# DM3370_Connector_B.net
KiCad netlist of a schematic drawn in Altium Designer
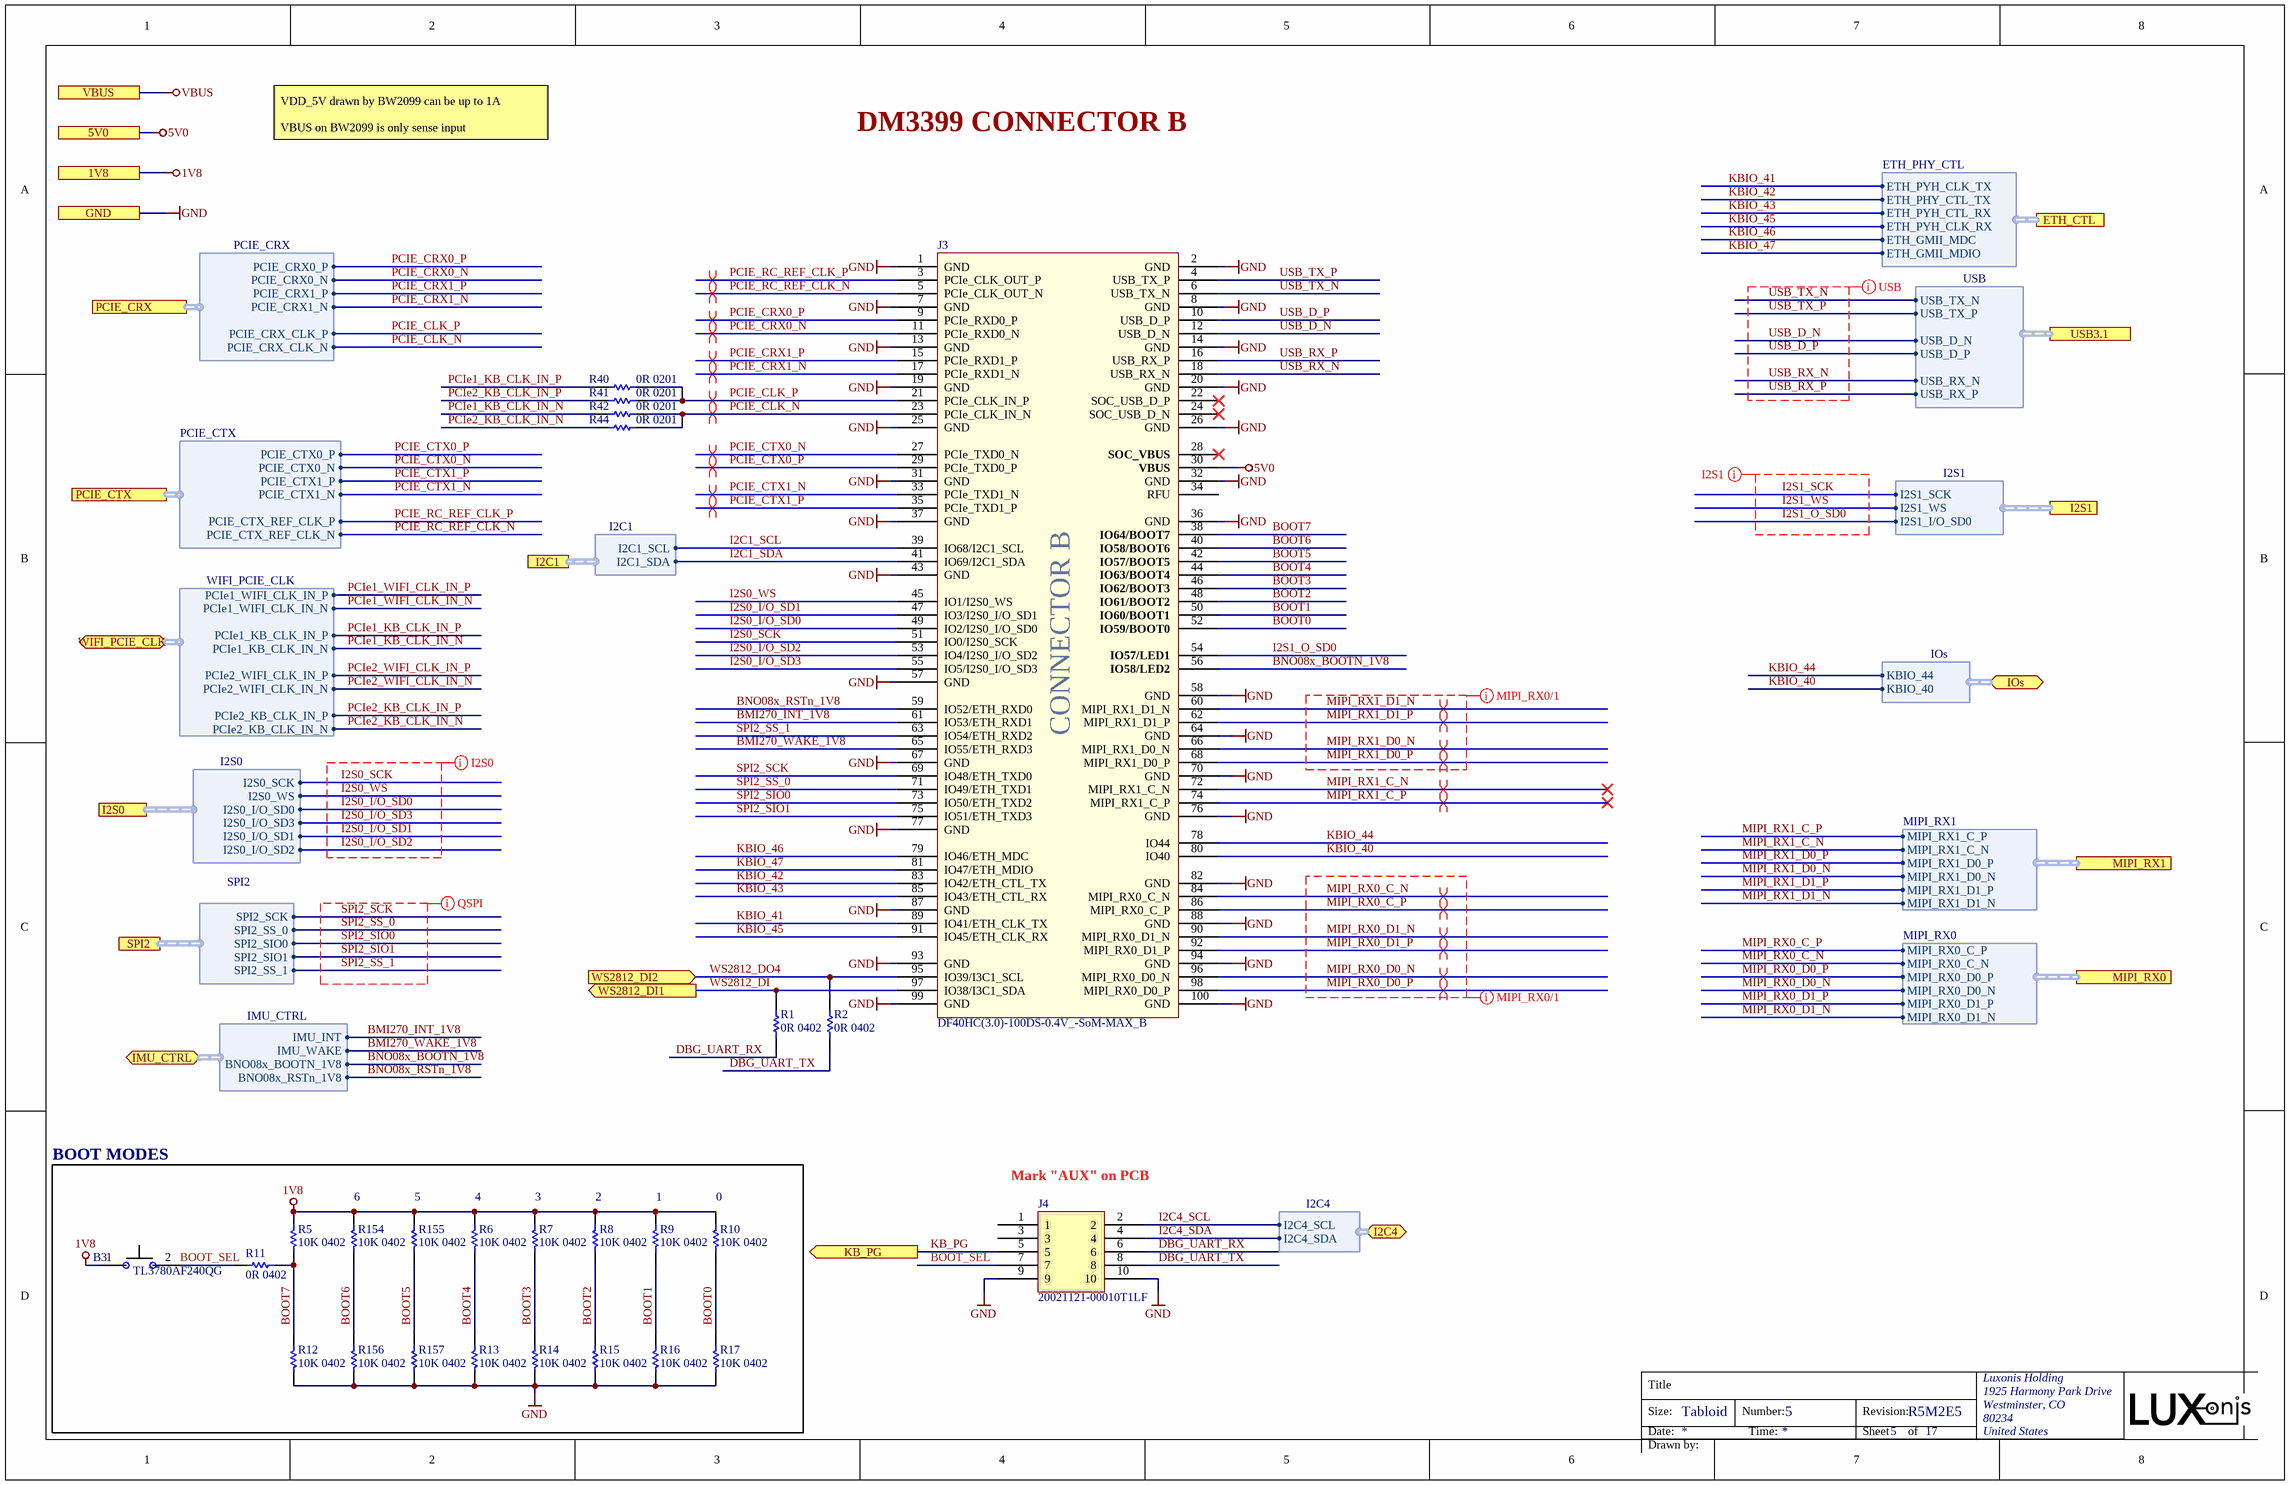
[diagram p0: DM3370_Connector_B.SchDoc]

(export (version "E")
  (design (tool "Eeschema 10.0.6"))
  (components
    (comp (ref "B3")
      (value "TL3780AF240QG")
      (footprint "TL3780AF240QG-Footprint-1")
      (libsource (lib "Luxonis LLC") (part "TL3780AF240QG"))
    )
    (comp (ref "J3")
      (value "DF40HC(3.0)-100DS-0.4V_-SoM-MAX_B")
      (footprint "SOM_MAX_CONN_B_DF40HC-3.0-100DS-0.4V_minpad")
      (description "OAK-SoM-MAX base board conn. B")
      (fields (field (name "SOURCE") "LuxonisMaster_nejc.SchLib"))
      (libsource (lib "Luxonis LLC") (part "DF40HC(3.0)-100DS-0.4V_-SoM-MAX_B"))
    )
    (comp (ref "J4")
      (value "20021121-00010T1LF")
      (footprint "LuxonisMaster:20021121-00010T1LF")
      (description "CONN HEADER SMD 10POS 1.27MM")
      (libsource (lib "LuxonisMaster") (part "20021121-00010T1LF"))
    )
    (comp (ref "R1")
      (value "0R 0402")
      (footprint "RES_Altium_Vault_Generic:RESC0402(1005)_L")
      (description "RES SMD 0 OHM JUMPER 1/16W 0402")
      (fields (field (name "TOLERANCE") "5%"))
      (libsource (lib "LuxonisMaster") (part "CRCW04020000Z0ED"))
    )
    (comp (ref "R2")
      (value "0R 0402")
      (footprint "RES_Altium_Vault_Generic:RESC0402(1005)_L")
      (description "RES SMD 0 OHM JUMPER 1/16W 0402")
      (fields (field (name "TOLERANCE") "5%"))
      (libsource (lib "LuxonisMaster") (part "CRCW04020000Z0ED"))
    )
    (comp (ref "R5")
      (value "10K 0402")
      (footprint "RES_Altium_Vault_Generic:RESC0402(1005)_L")
      (fields (field (name "TOLERANCE") "1%"))
      (libsource (lib "LuxonisMaster") (part "RC0402FR-1310KL"))
    )
    (comp (ref "R6")
      (value "10K 0402")
      (footprint "RES_Altium_Vault_Generic:RESC0402(1005)_L")
      (fields (field (name "TOLERANCE") "1%"))
      (libsource (lib "LuxonisMaster") (part "RC0402FR-1310KL"))
    )
    (comp (ref "R7")
      (value "10K 0402")
      (footprint "RES_Altium_Vault_Generic:RESC0402(1005)_L")
      (fields (field (name "TOLERANCE") "1%"))
      (libsource (lib "LuxonisMaster") (part "RC0402FR-1310KL"))
    )
    (comp (ref "R8")
      (value "10K 0402")
      (footprint "RES_Altium_Vault_Generic:RESC0402(1005)_L")
      (fields (field (name "TOLERANCE") "1%"))
      (libsource (lib "LuxonisMaster") (part "RC0402FR-1310KL"))
    )
    (comp (ref "R9")
      (value "10K 0402")
      (footprint "RES_Altium_Vault_Generic:RESC0402(1005)_L")
      (fields (field (name "TOLERANCE") "1%"))
      (libsource (lib "LuxonisMaster") (part "RC0402FR-1310KL"))
    )
    (comp (ref "R10")
      (value "10K 0402")
      (footprint "RES_Altium_Vault_Generic:RESC0402(1005)_L")
      (fields (field (name "TOLERANCE") "1%"))
      (libsource (lib "LuxonisMaster") (part "RC0402FR-1310KL"))
    )
    (comp (ref "R11")
      (value "0R 0402")
      (footprint "RES_Altium_Vault_Generic:RESC0402(1005)_L")
      (description "RES SMD 0 OHM JUMPER 1/16W 0402")
      (fields (field (name "TOLERANCE") "5%"))
      (libsource (lib "LuxonisMaster") (part "CRCW04020000Z0ED"))
    )
    (comp (ref "R12")
      (value "10K 0402")
      (footprint "RES_Altium_Vault_Generic:RESC0402(1005)_L")
      (fields (field (name "TOLERANCE") "1%"))
      (libsource (lib "LuxonisMaster") (part "RC0402FR-1310KL"))
    )
    (comp (ref "R13")
      (value "10K 0402")
      (footprint "RES_Altium_Vault_Generic:RESC0402(1005)_L")
      (fields (field (name "TOLERANCE") "1%"))
      (libsource (lib "LuxonisMaster") (part "RC0402FR-1310KL"))
    )
    (comp (ref "R14")
      (value "10K 0402")
      (footprint "RES_Altium_Vault_Generic:RESC0402(1005)_L")
      (fields (field (name "TOLERANCE") "1%"))
      (libsource (lib "LuxonisMaster") (part "RC0402FR-1310KL"))
    )
    (comp (ref "R15")
      (value "10K 0402")
      (footprint "RES_Altium_Vault_Generic:RESC0402(1005)_L")
      (fields (field (name "TOLERANCE") "1%"))
      (libsource (lib "LuxonisMaster") (part "RC0402FR-1310KL"))
    )
    (comp (ref "R16")
      (value "10K 0402")
      (footprint "RES_Altium_Vault_Generic:RESC0402(1005)_L")
      (fields (field (name "TOLERANCE") "1%"))
      (libsource (lib "LuxonisMaster") (part "RC0402FR-1310KL"))
    )
    (comp (ref "R17")
      (value "10K 0402")
      (footprint "RES_Altium_Vault_Generic:RESC0402(1005)_L")
      (fields (field (name "TOLERANCE") "1%"))
      (libsource (lib "LuxonisMaster") (part "RC0402FR-1310KL"))
    )
    (comp (ref "R40")
      (value "0R 0201")
      (footprint "RESC0201(0603)_L")
      (description "RES SMD 0 OHM JUMPER 1/16W 0201")
      (libsource (lib "LuxonisMaster") (part "CRCW02010000Z0ED"))
    )
    (comp (ref "R41")
      (value "0R 0201")
      (footprint "RESC0201(0603)_L")
      (description "RES SMD 0 OHM JUMPER 1/16W 0201")
      (libsource (lib "LuxonisMaster") (part "CRCW02010000Z0ED"))
    )
    (comp (ref "R42")
      (value "0R 0201")
      (footprint "RESC0201(0603)_L")
      (description "RES SMD 0 OHM JUMPER 1/16W 0201")
      (libsource (lib "LuxonisMaster") (part "CRCW02010000Z0ED"))
    )
    (comp (ref "R44")
      (value "0R 0201")
      (footprint "RESC0201(0603)_L")
      (description "RES SMD 0 OHM JUMPER 1/16W 0201")
      (libsource (lib "LuxonisMaster") (part "CRCW02010000Z0ED"))
    )
    (comp (ref "R154")
      (value "10K 0402")
      (footprint "RES_Altium_Vault_Generic:RESC0402(1005)_L")
      (fields (field (name "TOLERANCE") "1%"))
      (libsource (lib "LuxonisMaster") (part "RC0402FR-1310KL"))
    )
    (comp (ref "R155")
      (value "10K 0402")
      (footprint "RES_Altium_Vault_Generic:RESC0402(1005)_L")
      (fields (field (name "TOLERANCE") "1%"))
      (libsource (lib "LuxonisMaster") (part "RC0402FR-1310KL"))
    )
    (comp (ref "R156")
      (value "10K 0402")
      (footprint "RES_Altium_Vault_Generic:RESC0402(1005)_L")
      (fields (field (name "TOLERANCE") "1%"))
      (libsource (lib "LuxonisMaster") (part "RC0402FR-1310KL"))
    )
    (comp (ref "R157")
      (value "10K 0402")
      (footprint "RES_Altium_Vault_Generic:RESC0402(1005)_L")
      (fields (field (name "TOLERANCE") "1%"))
      (libsource (lib "LuxonisMaster") (part "RC0402FR-1310KL"))
    )
  )
  (nets
    (net (code "15") (name "/BMI270_INT_1V8") (class "Default")
      (node (ref "J3") (pin "61") (pinfunction "IO53/ETH_RXD1_61") (pintype "passive"))
    )
    (net (code "16") (name "/BMI270_WAKE_1V8") (class "Default")
      (node (ref "J3") (pin "65") (pinfunction "IO55/ETH_RXD3_65") (pintype "passive"))
    )
    (net (code "17") (name "/BNO08x_BOOTN_1V8") (class "Default")
      (node (ref "J3") (pin "56") (pinfunction "IO58/LED2_56") (pintype "passive"))
    )
    (net (code "18") (name "/BNO08x_RSTn_1V8") (class "Default")
      (node (ref "J3") (pin "59") (pinfunction "IO52/ETH_RXD0_59") (pintype "passive"))
    )
    (net (code "19") (name "/BOOT0") (class "Default")
      (node (ref "J3") (pin "52") (pinfunction "IO59/BOOT0_52") (pintype "passive"))
      (node (ref "R10") (pin "2") (pinfunction "2_2") (pintype "passive"))
      (node (ref "R17") (pin "1") (pinfunction "1_1") (pintype "passive"))
    )
    (net (code "20") (name "/BOOT1") (class "Default")
      (node (ref "J3") (pin "50") (pinfunction "IO60/BOOT1_50") (pintype "passive"))
      (node (ref "R16") (pin "1") (pinfunction "1_1") (pintype "passive"))
      (node (ref "R9") (pin "2") (pinfunction "2_2") (pintype "passive"))
    )
    (net (code "21") (name "/BOOT2") (class "Default")
      (node (ref "J3") (pin "48") (pinfunction "IO61/BOOT2_48") (pintype "passive"))
      (node (ref "R15") (pin "1") (pinfunction "1_1") (pintype "passive"))
      (node (ref "R8") (pin "2") (pinfunction "2_2") (pintype "passive"))
    )
    (net (code "22") (name "/BOOT3") (class "Default")
      (node (ref "J3") (pin "46") (pinfunction "IO62/BOOT3_46") (pintype "passive"))
      (node (ref "R14") (pin "1") (pinfunction "1_1") (pintype "passive"))
      (node (ref "R7") (pin "2") (pinfunction "2_2") (pintype "passive"))
    )
    (net (code "23") (name "/BOOT4") (class "Default")
      (node (ref "J3") (pin "44") (pinfunction "IO63/BOOT4_44") (pintype "passive"))
      (node (ref "R13") (pin "1") (pinfunction "1_1") (pintype "passive"))
      (node (ref "R6") (pin "2") (pinfunction "2_2") (pintype "passive"))
    )
    (net (code "24") (name "/BOOT5") (class "Default")
      (node (ref "J3") (pin "42") (pinfunction "IO57/BOOT5_42") (pintype "passive"))
      (node (ref "R155") (pin "2") (pinfunction "2_2") (pintype "passive"))
      (node (ref "R157") (pin "1") (pinfunction "1_1") (pintype "passive"))
    )
    (net (code "25") (name "/BOOT6") (class "Default")
      (node (ref "J3") (pin "40") (pinfunction "IO58/BOOT6_40") (pintype "passive"))
      (node (ref "R154") (pin "2") (pinfunction "2_2") (pintype "passive"))
      (node (ref "R156") (pin "1") (pinfunction "1_1") (pintype "passive"))
    )
    (net (code "26") (name "/BOOT7") (class "Default")
      (node (ref "J3") (pin "38") (pinfunction "IO64/BOOT7_38") (pintype "passive"))
      (node (ref "R11") (pin "2") (pinfunction "2_2") (pintype "passive"))
      (node (ref "R12") (pin "1") (pinfunction "1_1") (pintype "passive"))
      (node (ref "R5") (pin "2") (pinfunction "2_2") (pintype "passive"))
    )
    (net (code "27") (name "/BOOT_SEL") (class "Default")
      (node (ref "B3") (pin "2") (pinfunction "2_2") (pintype "passive"))
      (node (ref "J4") (pin "7") (pinfunction "7_7") (pintype "passive"))
      (node (ref "R11") (pin "1") (pinfunction "1_1") (pintype "passive"))
    )
    (net (code "28") (name "/DBG_UART_RX") (class "Default")
      (node (ref "J4") (pin "6") (pinfunction "6_6") (pintype "passive"))
      (node (ref "R1") (pin "1") (pinfunction "1_1") (pintype "passive"))
    )
    (net (code "29") (name "/DBG_UART_TX") (class "Default")
      (node (ref "J4") (pin "8") (pinfunction "8_8") (pintype "passive"))
      (node (ref "R2") (pin "1") (pinfunction "1_1") (pintype "passive"))
    )
    (net (code "30") (name "/I2C1_SCL") (class "Default")
      (node (ref "J3") (pin "39") (pinfunction "IO68/I2C1_SCL_39") (pintype "passive"))
    )
    (net (code "31") (name "/I2C1_SDA") (class "Default")
      (node (ref "J3") (pin "41") (pinfunction "IO69/I2C1_SDA_41") (pintype "passive"))
    )
    (net (code "32") (name "/I2C4_SCL") (class "Default")
      (node (ref "J4") (pin "2") (pinfunction "2_2") (pintype "passive"))
    )
    (net (code "33") (name "/I2C4_SDA") (class "Default")
      (node (ref "J4") (pin "4") (pinfunction "4_4") (pintype "passive"))
    )
    (net (code "34") (name "/I2S0_I{slash}O_SD0") (class "Default")
      (node (ref "J3") (pin "49") (pinfunction "IO2/I2S0_I/O_SD0_49") (pintype "passive"))
    )
    (net (code "35") (name "/I2S0_I{slash}O_SD1") (class "Default")
      (node (ref "J3") (pin "47") (pinfunction "IO3/I2S0_I/O_SD1_47") (pintype "passive"))
    )
    (net (code "36") (name "/I2S0_I{slash}O_SD2") (class "Default")
      (node (ref "J3") (pin "53") (pinfunction "IO4/I2S0_I/O_SD2_53") (pintype "passive"))
    )
    (net (code "37") (name "/I2S0_I{slash}O_SD3") (class "Default")
      (node (ref "J3") (pin "55") (pinfunction "IO5/I2S0_I/O_SD3_55") (pintype "passive"))
    )
    (net (code "38") (name "/I2S0_SCK") (class "Default")
      (node (ref "J3") (pin "51") (pinfunction "IO0/I2S0_SCK_51") (pintype "passive"))
    )
    (net (code "39") (name "/I2S0_WS") (class "Default")
      (node (ref "J3") (pin "45") (pinfunction "IO1/I2S0_WS_45") (pintype "passive"))
    )
    (net (code "40") (name "/I2S1_O_SD0") (class "Default")
      (node (ref "J3") (pin "54") (pinfunction "IO57/LED1_54") (pintype "passive"))
    )
    (net (code "43") (name "/KBIO_40") (class "Default")
      (node (ref "J3") (pin "80") (pinfunction "IO40_80") (pintype "passive"))
    )
    (net (code "44") (name "/KBIO_41") (class "Default")
      (node (ref "J3") (pin "89") (pinfunction "IO41/ETH_CLK_TX_89") (pintype "passive"))
    )
    (net (code "45") (name "/KBIO_42") (class "Default")
      (node (ref "J3") (pin "83") (pinfunction "IO42/ETH_CTL_TX_83") (pintype "passive"))
    )
    (net (code "46") (name "/KBIO_43") (class "Default")
      (node (ref "J3") (pin "85") (pinfunction "IO43/ETH_CTL_RX_85") (pintype "passive"))
    )
    (net (code "47") (name "/KBIO_44") (class "Default")
      (node (ref "J3") (pin "78") (pinfunction "IO44_78") (pintype "passive"))
    )
    (net (code "48") (name "/KBIO_45") (class "Default")
      (node (ref "J3") (pin "91") (pinfunction "IO45/ETH_CLK_RX_91") (pintype "passive"))
    )
    (net (code "49") (name "/KBIO_46") (class "Default")
      (node (ref "J3") (pin "79") (pinfunction "IO46/ETH_MDC_79") (pintype "passive"))
    )
    (net (code "50") (name "/KBIO_47") (class "Default")
      (node (ref "J3") (pin "81") (pinfunction "IO47/ETH_MDIO_81") (pintype "passive"))
    )
    (net (code "51") (name "/KB_PG") (class "Default")
      (node (ref "J4") (pin "5") (pinfunction "5_5") (pintype "passive"))
    )
    (net (code "52") (name "/MIPI_RX0_C_N") (class "Default")
      (node (ref "J3") (pin "84") (pinfunction "MIPI_RX0_C_N_84") (pintype "passive"))
    )
    (net (code "53") (name "/MIPI_RX0_C_P") (class "Default")
      (node (ref "J3") (pin "86") (pinfunction "MIPI_RX0_C_P_86") (pintype "passive"))
    )
    (net (code "54") (name "/MIPI_RX0_D0_N") (class "Default")
      (node (ref "J3") (pin "96") (pinfunction "MIPI_RX0_D0_N_96") (pintype "passive"))
    )
    (net (code "55") (name "/MIPI_RX0_D0_P") (class "Default")
      (node (ref "J3") (pin "98") (pinfunction "MIPI_RX0_D0_P_98") (pintype "passive"))
    )
    (net (code "56") (name "/MIPI_RX0_D1_N") (class "Default")
      (node (ref "J3") (pin "90") (pinfunction "MIPI_RX0_D1_N_90") (pintype "passive"))
    )
    (net (code "57") (name "/MIPI_RX0_D1_P") (class "Default")
      (node (ref "J3") (pin "92") (pinfunction "MIPI_RX0_D1_P_92") (pintype "passive"))
    )
    (net (code "58") (name "/MIPI_RX1_C_N") (class "Default")
      (node (ref "J3") (pin "72") (pinfunction "MIPI_RX1_C_N_72") (pintype "passive+no_connect"))
    )
    (net (code "59") (name "/MIPI_RX1_C_P") (class "Default")
      (node (ref "J3") (pin "74") (pinfunction "MIPI_RX1_C_P_74") (pintype "passive+no_connect"))
    )
    (net (code "60") (name "/MIPI_RX1_D0_N") (class "Default")
      (node (ref "J3") (pin "66") (pinfunction "MIPI_RX1_D0_N_66") (pintype "passive"))
    )
    (net (code "61") (name "/MIPI_RX1_D0_P") (class "Default")
      (node (ref "J3") (pin "68") (pinfunction "MIPI_RX1_D0_P_68") (pintype "passive"))
    )
    (net (code "62") (name "/MIPI_RX1_D1_N") (class "Default")
      (node (ref "J3") (pin "60") (pinfunction "MIPI_RX1_D1_N_60") (pintype "passive"))
    )
    (net (code "63") (name "/MIPI_RX1_D1_P") (class "Default")
      (node (ref "J3") (pin "62") (pinfunction "MIPI_RX1_D1_P_62") (pintype "passive"))
    )
    (net (code "64") (name "/PCIE_CLK_N") (class "Default")
      (node (ref "J3") (pin "23") (pinfunction "PCIe_CLK_IN_N_23") (pintype "passive"))
      (node (ref "R42") (pin "2") (pinfunction "2_2") (pintype "passive"))
      (node (ref "R44") (pin "2") (pinfunction "2_2") (pintype "passive"))
    )
    (net (code "65") (name "/PCIE_CLK_P") (class "Default")
      (node (ref "J3") (pin "21") (pinfunction "PCIe_CLK_IN_P_21") (pintype "passive"))
      (node (ref "R40") (pin "2") (pinfunction "2_2") (pintype "passive"))
      (node (ref "R41") (pin "2") (pinfunction "2_2") (pintype "passive"))
    )
    (net (code "66") (name "/PCIE_CRX0_N") (class "Default")
      (node (ref "J3") (pin "11") (pinfunction "PCIe_RXD0_N_11") (pintype "passive"))
    )
    (net (code "67") (name "/PCIE_CRX0_P") (class "Default")
      (node (ref "J3") (pin "9") (pinfunction "PCIe_RXD0_P_9") (pintype "passive"))
    )
    (net (code "68") (name "/PCIE_CRX1_N") (class "Default")
      (node (ref "J3") (pin "17") (pinfunction "PCIe_RXD1_N_17") (pintype "passive"))
    )
    (net (code "69") (name "/PCIE_CRX1_P") (class "Default")
      (node (ref "J3") (pin "15") (pinfunction "PCIe_RXD1_P_15") (pintype "passive"))
    )
    (net (code "70") (name "/PCIE_CTX0_N") (class "Default")
      (node (ref "J3") (pin "27") (pinfunction "PCIe_TXD0_N_27") (pintype "passive"))
    )
    (net (code "71") (name "/PCIE_CTX0_P") (class "Default")
      (node (ref "J3") (pin "29") (pinfunction "PCIe_TXD0_P_29") (pintype "passive"))
    )
    (net (code "72") (name "/PCIE_CTX1_N") (class "Default")
      (node (ref "J3") (pin "33") (pinfunction "PCIe_TXD1_N_33") (pintype "passive"))
    )
    (net (code "73") (name "/PCIE_CTX1_P") (class "Default")
      (node (ref "J3") (pin "35") (pinfunction "PCIe_TXD1_P_35") (pintype "passive"))
    )
    (net (code "74") (name "/PCIE_RC_REF_CLK_N") (class "Default")
      (node (ref "J3") (pin "5") (pinfunction "PCIe_CLK_OUT_N_5") (pintype "passive"))
    )
    (net (code "75") (name "/PCIE_RC_REF_CLK_P") (class "Default")
      (node (ref "J3") (pin "3") (pinfunction "PCIe_CLK_OUT_P_3") (pintype "passive"))
    )
    (net (code "76") (name "/PCIe1_KB_CLK_IN_N") (class "Default")
      (node (ref "R42") (pin "1") (pinfunction "1_1") (pintype "passive"))
    )
    (net (code "77") (name "/PCIe1_KB_CLK_IN_P") (class "Default")
      (node (ref "R40") (pin "1") (pinfunction "1_1") (pintype "passive"))
    )
    (net (code "80") (name "/PCIe2_KB_CLK_IN_N") (class "Default")
      (node (ref "R44") (pin "1") (pinfunction "1_1") (pintype "passive"))
    )
    (net (code "81") (name "/PCIe2_KB_CLK_IN_P") (class "Default")
      (node (ref "R41") (pin "1") (pinfunction "1_1") (pintype "passive"))
    )
    (net (code "84") (name "/SPI2_SCK") (class "Default")
      (node (ref "J3") (pin "69") (pinfunction "IO48/ETH_TXD0_69") (pintype "passive"))
    )
    (net (code "85") (name "/SPI2_SIO0") (class "Default")
      (node (ref "J3") (pin "73") (pinfunction "IO50/ETH_TXD2_73") (pintype "passive"))
    )
    (net (code "86") (name "/SPI2_SIO1") (class "Default")
      (node (ref "J3") (pin "75") (pinfunction "IO51/ETH_TXD3_75") (pintype "passive"))
    )
    (net (code "87") (name "/SPI2_SS_0") (class "Default")
      (node (ref "J3") (pin "71") (pinfunction "IO49/ETH_TXD1_71") (pintype "passive"))
    )
    (net (code "88") (name "/SPI2_SS_1") (class "Default")
      (node (ref "J3") (pin "63") (pinfunction "IO54/ETH_RXD2_63") (pintype "passive"))
    )
    (net (code "89") (name "/USB_D_N") (class "Default")
      (node (ref "J3") (pin "12") (pinfunction "USB_D_N_12") (pintype "passive"))
    )
    (net (code "90") (name "/USB_D_P") (class "Default")
      (node (ref "J3") (pin "10") (pinfunction "USB_D_P_10") (pintype "passive"))
    )
    (net (code "91") (name "/USB_RX_N") (class "Default")
      (node (ref "J3") (pin "18") (pinfunction "USB_RX_N_18") (pintype "passive"))
    )
    (net (code "92") (name "/USB_RX_P") (class "Default")
      (node (ref "J3") (pin "16") (pinfunction "USB_RX_P_16") (pintype "passive"))
    )
    (net (code "93") (name "/USB_TX_N") (class "Default")
      (node (ref "J3") (pin "6") (pinfunction "USB_TX_N_6") (pintype "passive"))
    )
    (net (code "94") (name "/USB_TX_P") (class "Default")
      (node (ref "J3") (pin "4") (pinfunction "USB_TX_P_4") (pintype "passive"))
    )
    (net (code "95") (name "/WS2812_DI") (class "Default")
      (node (ref "J3") (pin "97") (pinfunction "IO38/I3C1_SDA_97") (pintype "passive"))
      (node (ref "R1") (pin "2") (pinfunction "2_2") (pintype "passive"))
    )
    (net (code "96") (name "/WS2812_DO4") (class "Default")
      (node (ref "J3") (pin "95") (pinfunction "IO39/I3C1_SCL_95") (pintype "passive"))
      (node (ref "R2") (pin "2") (pinfunction "2_2") (pintype "passive"))
    )
    (net (code "111") (name "1V8") (class "Default")
      (node (ref "B3") (pin "1") (pinfunction "1_1") (pintype "passive"))
      (node (ref "R10") (pin "1") (pinfunction "1_1") (pintype "passive"))
      (node (ref "R154") (pin "1") (pinfunction "1_1") (pintype "passive"))
      (node (ref "R155") (pin "1") (pinfunction "1_1") (pintype "passive"))
      (node (ref "R5") (pin "1") (pinfunction "1_1") (pintype "passive"))
      (node (ref "R6") (pin "1") (pinfunction "1_1") (pintype "passive"))
      (node (ref "R7") (pin "1") (pinfunction "1_1") (pintype "passive"))
      (node (ref "R8") (pin "1") (pinfunction "1_1") (pintype "passive"))
      (node (ref "R9") (pin "1") (pinfunction "1_1") (pintype "passive"))
    )
    (net (code "112") (name "5V0") (class "Default")
      (node (ref "J3") (pin "30") (pinfunction "VBUS_30") (pintype "passive"))
    )
    (net (code "113") (name "GND") (class "Default")
      (node (ref "J3") (pin "1") (pinfunction "GND_1") (pintype "passive"))
      (node (ref "J3") (pin "100") (pinfunction "GND_100") (pintype "passive"))
      (node (ref "J3") (pin "13") (pinfunction "GND_13") (pintype "passive"))
      (node (ref "J3") (pin "14") (pinfunction "GND_14") (pintype "passive"))
      (node (ref "J3") (pin "19") (pinfunction "GND_19") (pintype "passive"))
      (node (ref "J3") (pin "2") (pinfunction "GND_2") (pintype "passive"))
      (node (ref "J3") (pin "20") (pinfunction "GND_20") (pintype "passive"))
      (node (ref "J3") (pin "25") (pinfunction "GND_25") (pintype "passive"))
      (node (ref "J3") (pin "26") (pinfunction "GND_26") (pintype "passive"))
      (node (ref "J3") (pin "31") (pinfunction "GND_31") (pintype "passive"))
      (node (ref "J3") (pin "32") (pinfunction "GND_32") (pintype "passive"))
      (node (ref "J3") (pin "36") (pinfunction "GND_36") (pintype "passive"))
      (node (ref "J3") (pin "37") (pinfunction "GND_37") (pintype "passive"))
      (node (ref "J3") (pin "43") (pinfunction "GND_43") (pintype "passive"))
      (node (ref "J3") (pin "57") (pinfunction "GND_57") (pintype "passive"))
      (node (ref "J3") (pin "58") (pinfunction "GND_58") (pintype "passive"))
      (node (ref "J3") (pin "64") (pinfunction "GND_64") (pintype "passive"))
      (node (ref "J3") (pin "67") (pinfunction "GND_67") (pintype "passive"))
      (node (ref "J3") (pin "7") (pinfunction "GND_7") (pintype "passive"))
      (node (ref "J3") (pin "70") (pinfunction "GND_70") (pintype "passive"))
      (node (ref "J3") (pin "76") (pinfunction "GND_76") (pintype "passive"))
      (node (ref "J3") (pin "77") (pinfunction "GND_77") (pintype "passive"))
      (node (ref "J3") (pin "8") (pinfunction "GND_8") (pintype "passive"))
      (node (ref "J3") (pin "82") (pinfunction "GND_82") (pintype "passive"))
      (node (ref "J3") (pin "87") (pinfunction "GND_87") (pintype "passive"))
      (node (ref "J3") (pin "88") (pinfunction "GND_88") (pintype "passive"))
      (node (ref "J3") (pin "93") (pinfunction "GND_93") (pintype "passive"))
      (node (ref "J3") (pin "94") (pinfunction "GND_94") (pintype "passive"))
      (node (ref "J3") (pin "99") (pinfunction "GND_99") (pintype "passive"))
      (node (ref "J4") (pin "10") (pinfunction "10_10") (pintype "passive"))
      (node (ref "J4") (pin "9") (pinfunction "9_9") (pintype "passive"))
      (node (ref "R12") (pin "2") (pinfunction "2_2") (pintype "passive"))
      (node (ref "R13") (pin "2") (pinfunction "2_2") (pintype "passive"))
      (node (ref "R14") (pin "2") (pinfunction "2_2") (pintype "passive"))
      (node (ref "R15") (pin "2") (pinfunction "2_2") (pintype "passive"))
      (node (ref "R156") (pin "2") (pinfunction "2_2") (pintype "passive"))
      (node (ref "R157") (pin "2") (pinfunction "2_2") (pintype "passive"))
      (node (ref "R16") (pin "2") (pinfunction "2_2") (pintype "passive"))
      (node (ref "R17") (pin "2") (pinfunction "2_2") (pintype "passive"))
    )
    (net (code "115") (name "unconnected-(J3-RFU-Pad34)") (class "Default")
      (node (ref "J3") (pin "34") (pinfunction "RFU_34") (pintype "passive"))
    )
    (net (code "116") (name "unconnected-(J3-SOC_USB_D_N-Pad24)") (class "Default")
      (node (ref "J3") (pin "24") (pinfunction "SOC_USB_D_N_24") (pintype "passive+no_connect"))
    )
    (net (code "117") (name "unconnected-(J3-SOC_USB_D_P-Pad22)") (class "Default")
      (node (ref "J3") (pin "22") (pinfunction "SOC_USB_D_P_22") (pintype "passive+no_connect"))
    )
    (net (code "118") (name "unconnected-(J3-SOC_VBUS-Pad28)") (class "Default")
      (node (ref "J3") (pin "28") (pinfunction "SOC_VBUS_28") (pintype "passive+no_connect"))
    )
    (net (code "119") (name "unconnected-(J4-Pad1)") (class "Default")
      (node (ref "J4") (pin "1") (pinfunction "1_1") (pintype "passive"))
    )
    (net (code "120") (name "unconnected-(J4-Pad3)") (class "Default")
      (node (ref "J4") (pin "3") (pinfunction "3_3") (pintype "passive"))
    )
  )
)
